# coil_adapter.net
KiCad netlist of a schematic drawn in EAGLE
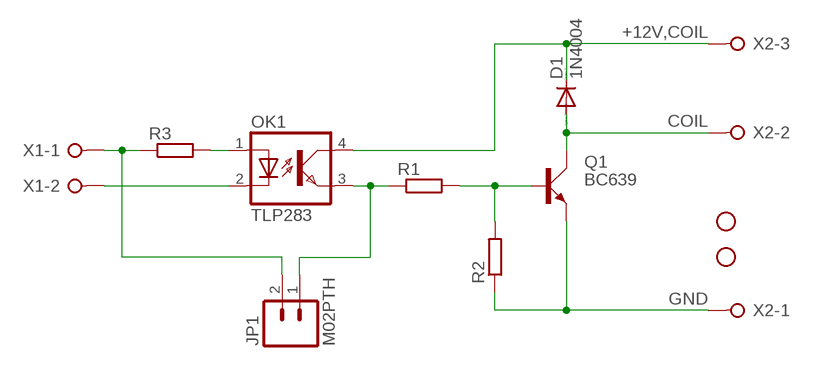
[diagram p0: schematic, sheet 1]

(export (version "E")
  (design (tool "Eeschema 10.0.6"))
  (components
    (comp (ref "D1")
      (value "1N4004")
      (footprint "eagle-import:DO41-10")
      (libsource (lib "eagle-import") (part "1N4004"))
    )
    (comp (ref "JP1")
      (value "M02PTH")
      (footprint "eagle-import:1X02")
      (libsource (lib "eagle-import") (part "M02PTH"))
    )
    (comp (ref "OK1")
      (value "TLP283")
      (footprint "eagle-import:MINI-FLAT-4")
      (libsource (lib "eagle-import") (part "TLP283"))
    )
    (comp (ref "Q1")
      (value "BC639")
      (footprint "eagle-import:SOT54D")
      (libsource (lib "eagle-import") (part "BC639"))
    )
    (comp (ref "R1")
      (value "R-EU_R1206")
      (footprint "eagle-import:R1206")
      (libsource (lib "eagle-import") (part "R-EU_R1206"))
    )
    (comp (ref "R2")
      (value "R-EU_R1206")
      (footprint "eagle-import:R1206")
      (libsource (lib "eagle-import") (part "R-EU_R1206"))
    )
    (comp (ref "R3")
      (value "R-EU_R1206")
      (footprint "eagle-import:R1206")
      (libsource (lib "eagle-import") (part "R-EU_R1206"))
    )
    (comp (ref "STANDOFF1")
      (value "STAND-OFF")
      (footprint "eagle-import:STAND-OFF")
      (libsource (lib "eagle-import") (part "STAND-OFF"))
    )
    (comp (ref "STANDOFF2")
      (value "STAND-OFF")
      (footprint "eagle-import:STAND-OFF")
      (libsource (lib "eagle-import") (part "STAND-OFF"))
    )
    (comp (ref "X1")
      (value "W237-02P")
      (footprint "eagle-import:W237-132")
      (libsource (lib "eagle-import") (part "W237-02P"))
    )
    (comp (ref "X2")
      (value "W237-03P")
      (footprint "eagle-import:W237-133")
      (libsource (lib "eagle-import") (part "W237-03P"))
    )
  )
  (nets
    (net (code "1") (name "/+12V,COIL") (class "Default")
      (node (ref "D1") (pin "C") (pinfunction "C_C") (pintype "passive"))
      (node (ref "OK1") (pin "4") (pinfunction "COL_4") (pintype "passive"))
      (node (ref "X2") (pin "3") (pinfunction "KL_3") (pintype "passive"))
    )
    (net (code "2") (name "/COIL") (class "Default")
      (node (ref "D1") (pin "A") (pinfunction "A_A") (pintype "passive"))
      (node (ref "Q1") (pin "C") (pinfunction "C_C") (pintype "passive"))
      (node (ref "X2") (pin "2") (pinfunction "KL_2") (pintype "passive"))
    )
    (net (code "3") (name "/GND") (class "Default")
      (node (ref "Q1") (pin "E") (pinfunction "E_E") (pintype "passive"))
      (node (ref "R2") (pin "1") (pinfunction "1_1") (pintype "passive"))
      (node (ref "X2") (pin "1") (pinfunction "KL_1") (pintype "passive"))
    )
    (net (code "4") (name "Net-(OK1-A)") (class "Default")
      (node (ref "OK1") (pin "1") (pinfunction "A_1") (pintype "passive"))
      (node (ref "R3") (pin "2") (pinfunction "2_2") (pintype "passive"))
    )
    (net (code "5") (name "Net-(OK1-C)") (class "Default")
      (node (ref "OK1") (pin "2") (pinfunction "C_2") (pintype "passive"))
      (node (ref "X1") (pin "2") (pinfunction "KL_2") (pintype "passive"))
    )
    (net (code "6") (name "Net-(OK1-EMIT)") (class "Default")
      (node (ref "JP1") (pin "1") (pinfunction "1_1") (pintype "passive"))
      (node (ref "OK1") (pin "3") (pinfunction "EMIT_3") (pintype "passive"))
      (node (ref "R1") (pin "1") (pinfunction "1_1") (pintype "passive"))
    )
    (net (code "7") (name "Net-(Q1-PadB)") (class "Default")
      (node (ref "Q1") (pin "B") (pinfunction "B_B") (pintype "passive"))
      (node (ref "R1") (pin "2") (pinfunction "2_2") (pintype "passive"))
      (node (ref "R2") (pin "2") (pinfunction "2_2") (pintype "passive"))
    )
    (net (code "8") (name "Net-(X1A-KL)") (class "Default")
      (node (ref "JP1") (pin "2") (pinfunction "2_2") (pintype "passive"))
      (node (ref "R3") (pin "1") (pinfunction "1_1") (pintype "passive"))
      (node (ref "X1") (pin "1") (pinfunction "KL_1") (pintype "passive"))
    )
  )
)
